# SCH_Data_Logging_system_Schematic_Rev_1_.net
KiCad netlist of a schematic drawn in EasyEDA
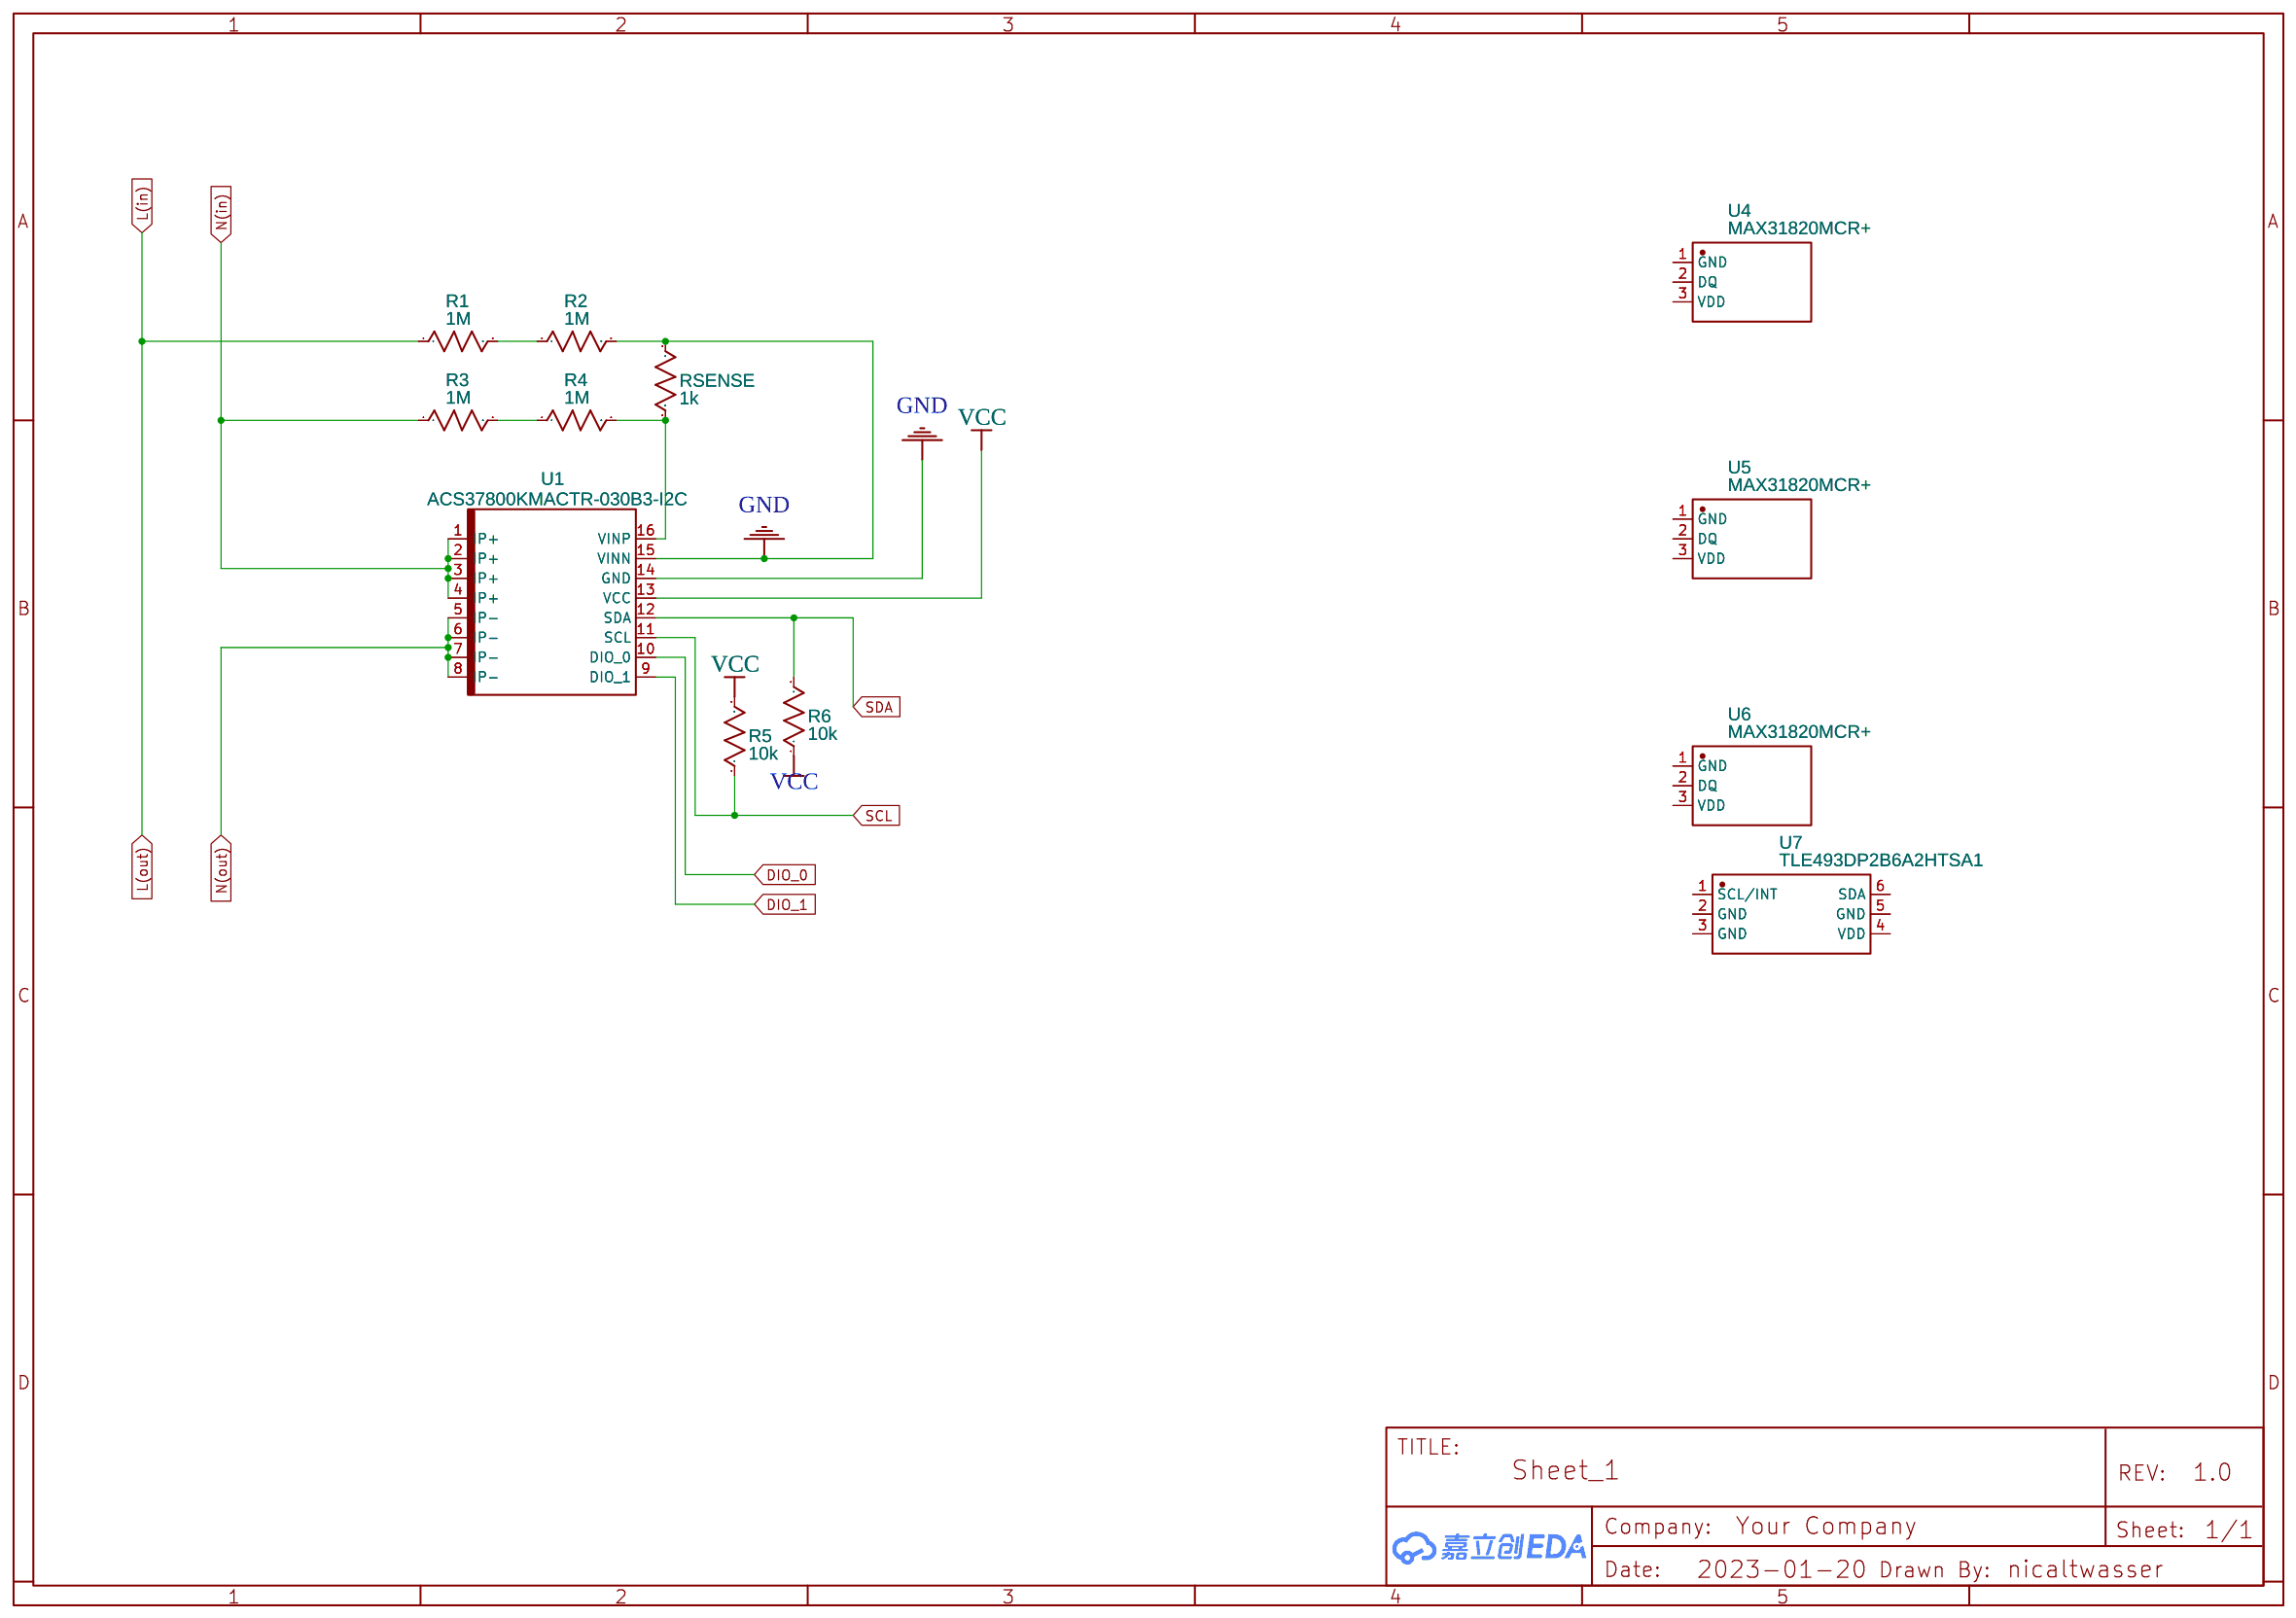
[diagram p0: Sheet_1]
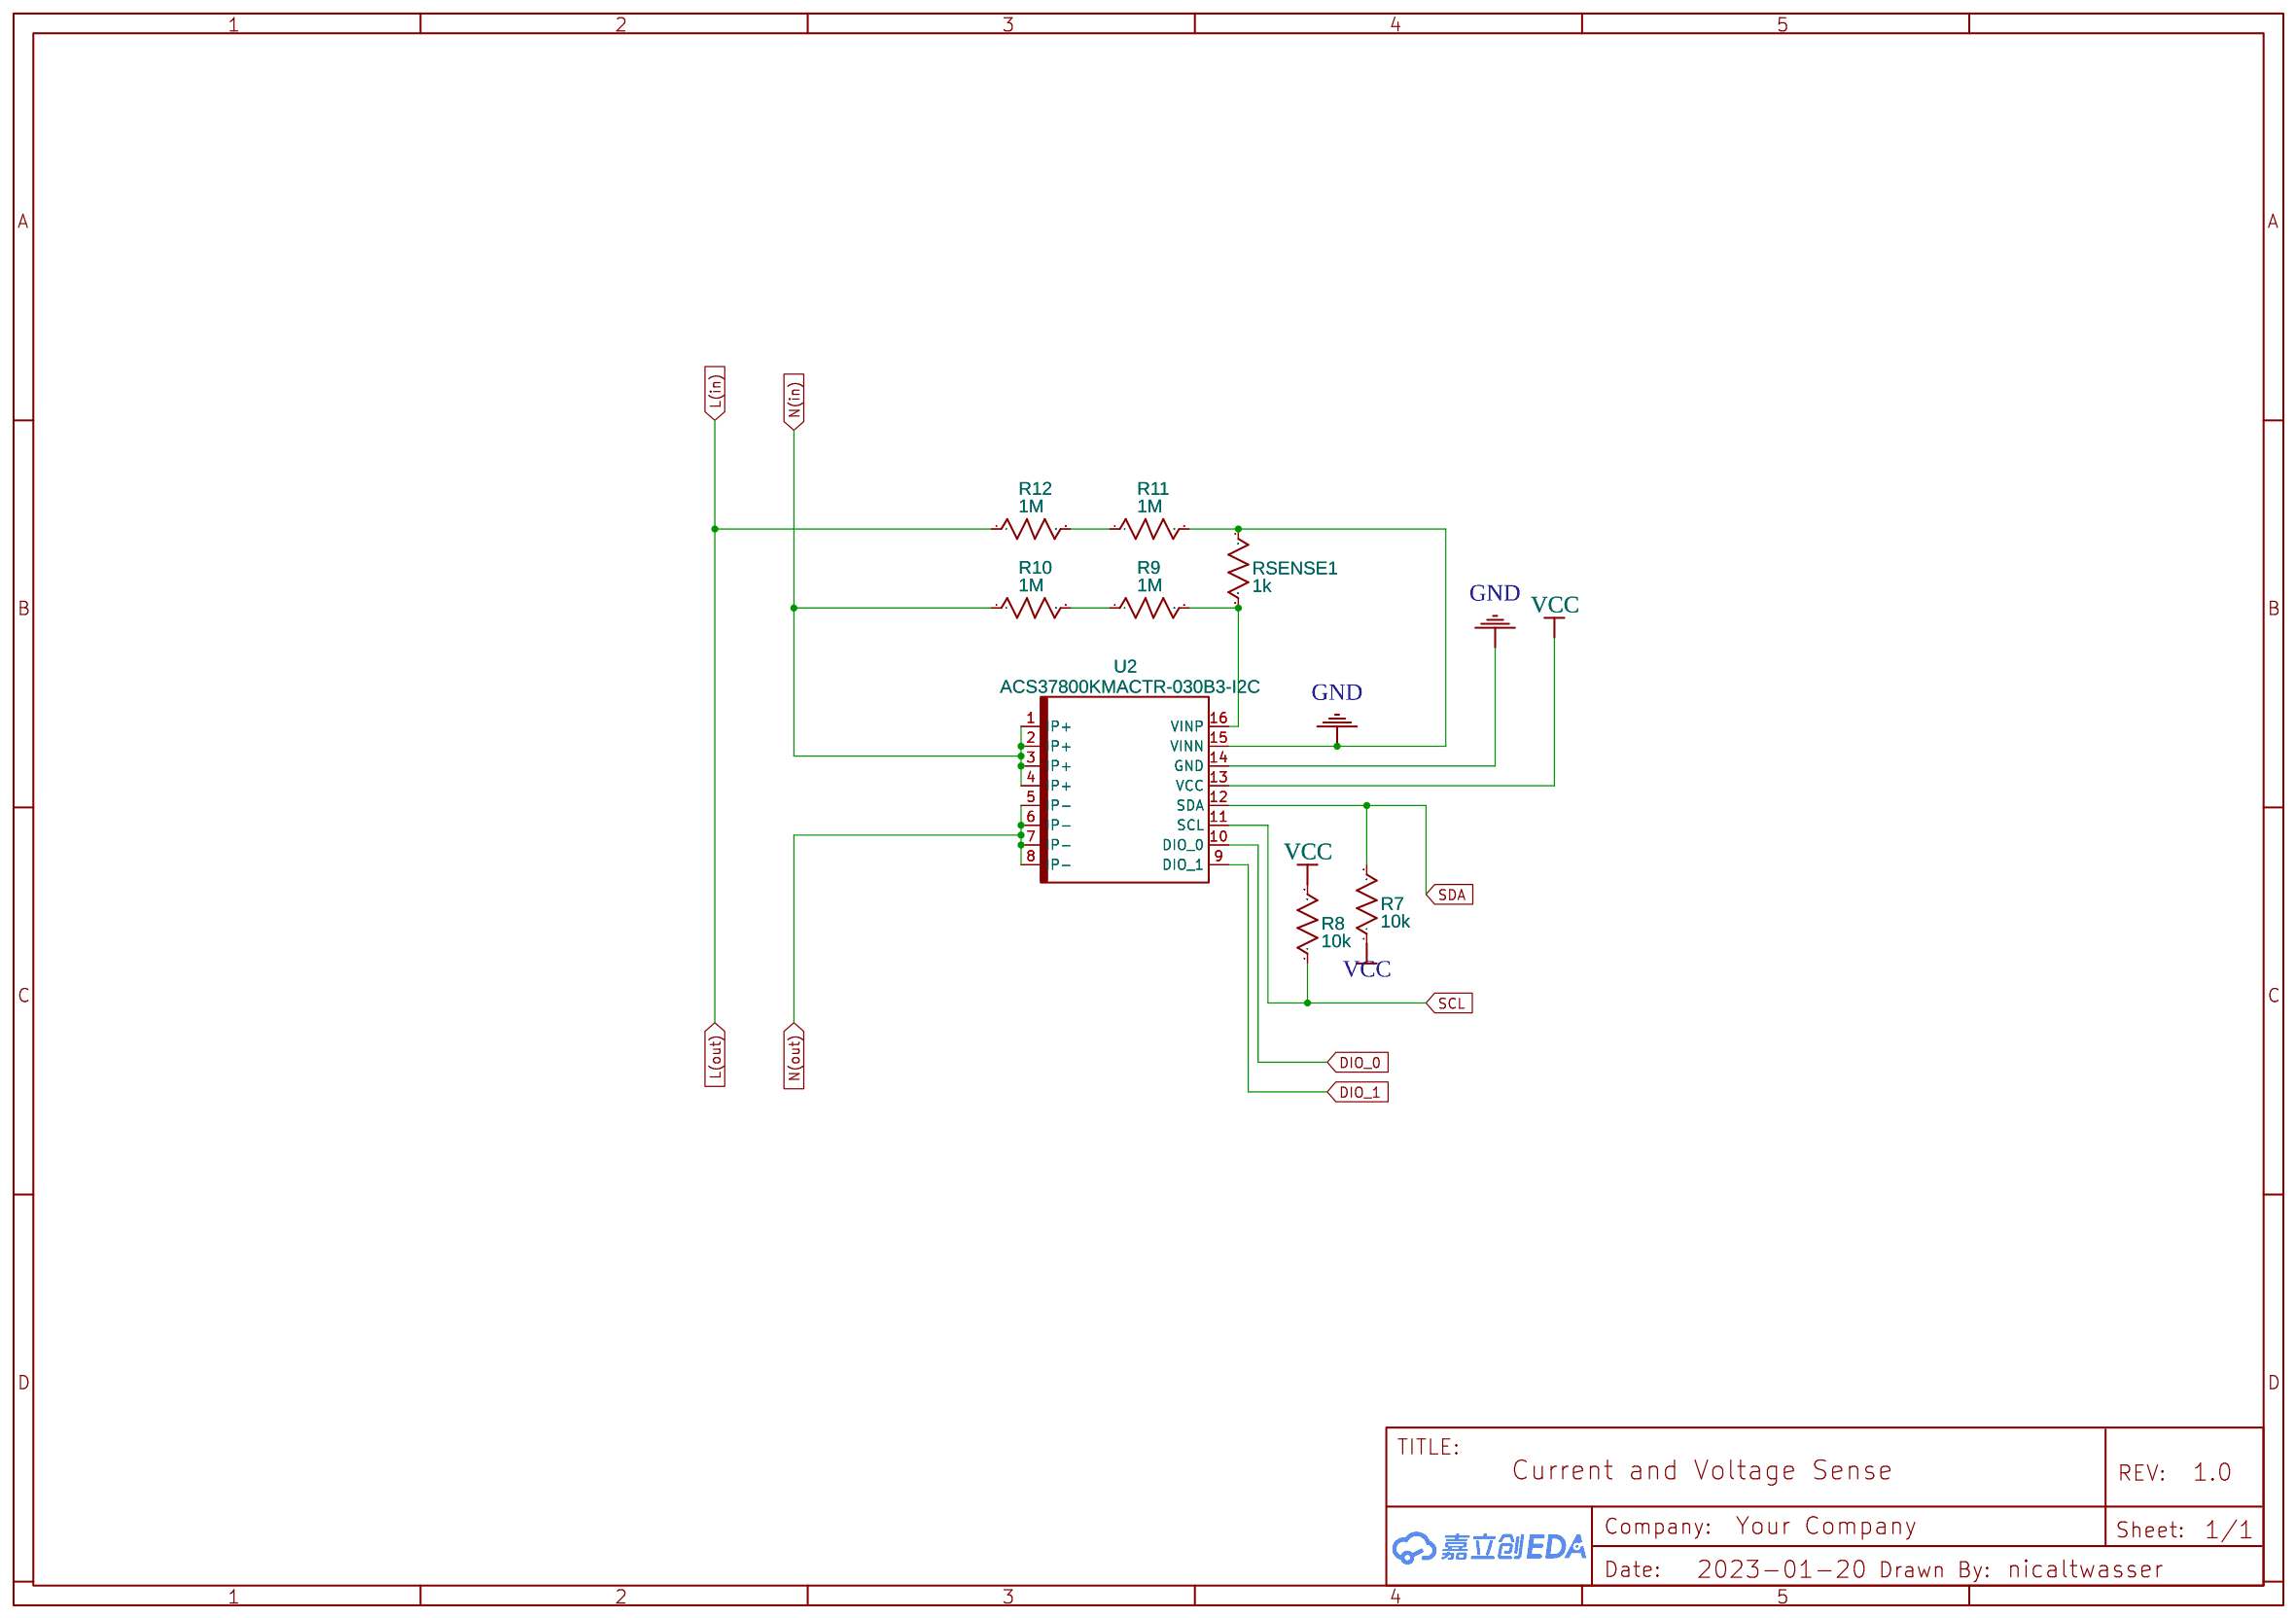
[diagram p1: Sheet_2]

(export (version "E")
  (design (tool "Eeschema 10.0.6"))
  (components
    (comp (ref "R1") (value "1M") (libsource (lib "") (part "R_0603_US")))
    (comp (ref "R2") (value "1M") (libsource (lib "") (part "R_0603_US")))
    (comp (ref "R3") (value "1M") (libsource (lib "") (part "R_0603_US")))
    (comp (ref "R4") (value "1M") (libsource (lib "") (part "R_0603_US")))
    (comp (ref "R5") (value "10k") (libsource (lib "") (part "R_0603_US_1")))
    (comp (ref "R6") (value "10k") (libsource (lib "") (part "R_0603_US_1")))
    (comp (ref "RSENSE") (value "1k") (libsource (lib "") (part "R_0603_US_2")))
    (comp (ref "U1")
      (value "ACS37800KMACTR-030B3-I2C")
      (libsource (lib "") (part "ACS37800KMACTR-030B3-I2C"))
    )
    (comp (ref "U4")
      (value "MAX31820MCR+")
      (fields (field (name "BOM_Supplier Part") "C190293"))
      (libsource (lib "") (part "MAX31820MCR+"))
    )
    (comp (ref "U5")
      (value "MAX31820MCR+")
      (fields (field (name "BOM_Supplier Part") "C190293"))
      (libsource (lib "") (part "MAX31820MCR+"))
    )
    (comp (ref "U6")
      (value "MAX31820MCR+")
      (fields (field (name "BOM_Supplier Part") "C190293"))
      (libsource (lib "") (part "MAX31820MCR+"))
    )
    (comp (ref "U7")
      (value "TLE493DP2B6A2HTSA1")
      (fields (field (name "BOM_Supplier Part") "C3716129"))
      (libsource (lib "") (part "TLE493DP2B6A2HTSA1"))
    )
    (comp (ref "R7") (value "10k") (libsource (lib "") (part "R_0603_US_1")))
    (comp (ref "R8") (value "10k") (libsource (lib "") (part "R_0603_US_1")))
    (comp (ref "R9") (value "1M") (libsource (lib "") (part "R_0603_US")))
    (comp (ref "R10") (value "1M") (libsource (lib "") (part "R_0603_US")))
    (comp (ref "R11") (value "1M") (libsource (lib "") (part "R_0603_US")))
    (comp (ref "R12") (value "1M") (libsource (lib "") (part "R_0603_US")))
    (comp (ref "RSENSE1") (value "1k") (libsource (lib "") (part "R_0603_US_2")))
    (comp (ref "U2")
      (value "ACS37800KMACTR-030B3-I2C")
      (libsource (lib "") (part "ACS37800KMACTR-030B3-I2C"))
    )
  )
  (nets
    (net (code "1") (name "DIO_0") (class "Default")
      (node (ref "U1") (pin "10") (pinfunction "DIO_0_10") (pintype "unspecified"))
      (node (ref "U2") (pin "10") (pinfunction "DIO_0_10") (pintype "unspecified"))
    )
    (net (code "2") (name "DIO_1") (class "Default")
      (node (ref "U1") (pin "9") (pinfunction "DIO_1_9") (pintype "unspecified"))
      (node (ref "U2") (pin "9") (pinfunction "DIO_1_9") (pintype "unspecified"))
    )
    (net (code "3") (name "GND") (class "Default")
      (node (ref "R11") (pin "2") (pinfunction "2_2") (pintype "unspecified"))
      (node (ref "R2") (pin "2") (pinfunction "2_2") (pintype "unspecified"))
      (node (ref "RSENSE") (pin "1") (pinfunction "1_1") (pintype "unspecified"))
      (node (ref "RSENSE1") (pin "1") (pinfunction "1_1") (pintype "unspecified"))
      (node (ref "U1") (pin "14") (pinfunction "GND_14") (pintype "unspecified"))
      (node (ref "U1") (pin "15") (pinfunction "VINN_15") (pintype "unspecified"))
      (node (ref "U2") (pin "14") (pinfunction "GND_14") (pintype "unspecified"))
      (node (ref "U2") (pin "15") (pinfunction "VINN_15") (pintype "unspecified"))
    )
    (net (code "4") (name "L(in)") (class "Default")
      (node (ref "R1") (pin "1") (pinfunction "1_1") (pintype "unspecified"))
      (node (ref "R12") (pin "1") (pinfunction "1_1") (pintype "unspecified"))
    )
    (net (code "5") (name "N(in)") (class "Default")
      (node (ref "R10") (pin "1") (pinfunction "1_1") (pintype "unspecified"))
      (node (ref "R3") (pin "1") (pinfunction "1_1") (pintype "unspecified"))
      (node (ref "U1") (pin "1") (pinfunction "IP+_1") (pintype "unspecified"))
      (node (ref "U1") (pin "2") (pinfunction "IP+_2") (pintype "unspecified"))
      (node (ref "U1") (pin "3") (pinfunction "IP+_3") (pintype "unspecified"))
      (node (ref "U1") (pin "4") (pinfunction "IP+_4") (pintype "unspecified"))
      (node (ref "U2") (pin "1") (pinfunction "IP+_1") (pintype "unspecified"))
      (node (ref "U2") (pin "2") (pinfunction "IP+_2") (pintype "unspecified"))
      (node (ref "U2") (pin "3") (pinfunction "IP+_3") (pintype "unspecified"))
      (node (ref "U2") (pin "4") (pinfunction "IP+_4") (pintype "unspecified"))
    )
    (net (code "6") (name "N(out)") (class "Default")
      (node (ref "U1") (pin "5") (pinfunction "IP-_5") (pintype "unspecified"))
      (node (ref "U1") (pin "6") (pinfunction "IP-_6") (pintype "unspecified"))
      (node (ref "U1") (pin "7") (pinfunction "IP-_7") (pintype "unspecified"))
      (node (ref "U1") (pin "8") (pinfunction "IP-_8") (pintype "unspecified"))
      (node (ref "U2") (pin "5") (pinfunction "IP-_5") (pintype "unspecified"))
      (node (ref "U2") (pin "6") (pinfunction "IP-_6") (pintype "unspecified"))
      (node (ref "U2") (pin "7") (pinfunction "IP-_7") (pintype "unspecified"))
      (node (ref "U2") (pin "8") (pinfunction "IP-_8") (pintype "unspecified"))
    )
    (net (code "7") (name "Net-(R1-Pad2)") (class "Default")
      (node (ref "R1") (pin "2") (pinfunction "2_2") (pintype "unspecified"))
      (node (ref "R2") (pin "1") (pinfunction "1_1") (pintype "unspecified"))
    )
    (net (code "8") (name "Net-(R3-Pad2)") (class "Default")
      (node (ref "R3") (pin "2") (pinfunction "2_2") (pintype "unspecified"))
      (node (ref "R4") (pin "1") (pinfunction "1_1") (pintype "unspecified"))
    )
    (net (code "9") (name "Net-(R10-Pad2)") (class "Default")
      (node (ref "R10") (pin "2") (pinfunction "2_2") (pintype "unspecified"))
      (node (ref "R9") (pin "1") (pinfunction "1_1") (pintype "unspecified"))
    )
    (net (code "10") (name "Net-(R11-Pad1)") (class "Default")
      (node (ref "R11") (pin "1") (pinfunction "1_1") (pintype "unspecified"))
      (node (ref "R12") (pin "2") (pinfunction "2_2") (pintype "unspecified"))
    )
    (net (code "11") (name "Net-(U1-VINP)") (class "Default")
      (node (ref "R4") (pin "2") (pinfunction "2_2") (pintype "unspecified"))
      (node (ref "RSENSE") (pin "2") (pinfunction "2_2") (pintype "unspecified"))
      (node (ref "U1") (pin "16") (pinfunction "VINP_16") (pintype "unspecified"))
    )
    (net (code "12") (name "Net-(U2-VINP)") (class "Default")
      (node (ref "R9") (pin "2") (pinfunction "2_2") (pintype "unspecified"))
      (node (ref "RSENSE1") (pin "2") (pinfunction "2_2") (pintype "unspecified"))
      (node (ref "U2") (pin "16") (pinfunction "VINP_16") (pintype "unspecified"))
    )
    (net (code "13") (name "SCL") (class "Default")
      (node (ref "R5") (pin "1") (pinfunction "1_1") (pintype "unspecified"))
      (node (ref "R8") (pin "1") (pinfunction "1_1") (pintype "unspecified"))
      (node (ref "U1") (pin "11") (pinfunction "SCL_11") (pintype "unspecified"))
      (node (ref "U2") (pin "11") (pinfunction "SCL_11") (pintype "unspecified"))
    )
    (net (code "14") (name "SDA") (class "Default")
      (node (ref "R6") (pin "2") (pinfunction "2_2") (pintype "unspecified"))
      (node (ref "R7") (pin "2") (pinfunction "2_2") (pintype "unspecified"))
      (node (ref "U1") (pin "12") (pinfunction "SDA_12") (pintype "unspecified"))
      (node (ref "U2") (pin "12") (pinfunction "SDA_12") (pintype "unspecified"))
    )
    (net (code "15") (name "VCC") (class "Default")
      (node (ref "R5") (pin "2") (pinfunction "2_2") (pintype "unspecified"))
      (node (ref "R6") (pin "1") (pinfunction "1_1") (pintype "unspecified"))
      (node (ref "R7") (pin "1") (pinfunction "1_1") (pintype "unspecified"))
      (node (ref "R8") (pin "2") (pinfunction "2_2") (pintype "unspecified"))
      (node (ref "U1") (pin "13") (pinfunction "VCC_13") (pintype "unspecified"))
      (node (ref "U2") (pin "13") (pinfunction "VCC_13") (pintype "unspecified"))
    )
    (net (code "16") (name "unconnected-(U4-DQ-Pad2)") (class "Default")
      (node (ref "U4") (pin "2") (pinfunction "DQ_2") (pintype "unspecified"))
    )
    (net (code "17") (name "unconnected-(U4-GND-Pad1)") (class "Default")
      (node (ref "U4") (pin "1") (pinfunction "GND_1") (pintype "unspecified"))
    )
    (net (code "18") (name "unconnected-(U4-VDD-Pad3)") (class "Default")
      (node (ref "U4") (pin "3") (pinfunction "VDD_3") (pintype "unspecified"))
    )
    (net (code "19") (name "unconnected-(U5-DQ-Pad2)") (class "Default")
      (node (ref "U5") (pin "2") (pinfunction "DQ_2") (pintype "unspecified"))
    )
    (net (code "20") (name "unconnected-(U5-GND-Pad1)") (class "Default")
      (node (ref "U5") (pin "1") (pinfunction "GND_1") (pintype "unspecified"))
    )
    (net (code "21") (name "unconnected-(U5-VDD-Pad3)") (class "Default")
      (node (ref "U5") (pin "3") (pinfunction "VDD_3") (pintype "unspecified"))
    )
    (net (code "22") (name "unconnected-(U6-DQ-Pad2)") (class "Default")
      (node (ref "U6") (pin "2") (pinfunction "DQ_2") (pintype "unspecified"))
    )
    (net (code "23") (name "unconnected-(U6-GND-Pad1)") (class "Default")
      (node (ref "U6") (pin "1") (pinfunction "GND_1") (pintype "unspecified"))
    )
    (net (code "24") (name "unconnected-(U6-VDD-Pad3)") (class "Default")
      (node (ref "U6") (pin "3") (pinfunction "VDD_3") (pintype "unspecified"))
    )
    (net (code "25") (name "unconnected-(U7-GND-Pad2)") (class "Default")
      (node (ref "U7") (pin "2") (pinfunction "GND_2") (pintype "unspecified"))
    )
    (net (code "26") (name "unconnected-(U7-GND-Pad3)") (class "Default")
      (node (ref "U7") (pin "3") (pinfunction "GND_3") (pintype "unspecified"))
    )
    (net (code "27") (name "unconnected-(U7-GND-Pad5)") (class "Default")
      (node (ref "U7") (pin "5") (pinfunction "GND_5") (pintype "unspecified"))
    )
    (net (code "28") (name "unconnected-(U7-SCL{slash}INT-Pad1)") (class "Default")
      (node (ref "U7") (pin "1") (pinfunction "SCL/INT_1") (pintype "unspecified"))
    )
    (net (code "29") (name "unconnected-(U7-SDA-Pad6)") (class "Default")
      (node (ref "U7") (pin "6") (pinfunction "SDA_6") (pintype "unspecified"))
    )
    (net (code "30") (name "unconnected-(U7-VDD-Pad4)") (class "Default")
      (node (ref "U7") (pin "4") (pinfunction "VDD_4") (pintype "unspecified"))
    )
  )
)
